# Quad_ESC_controller.net
KiCad netlist of a schematic drawn in EAGLE
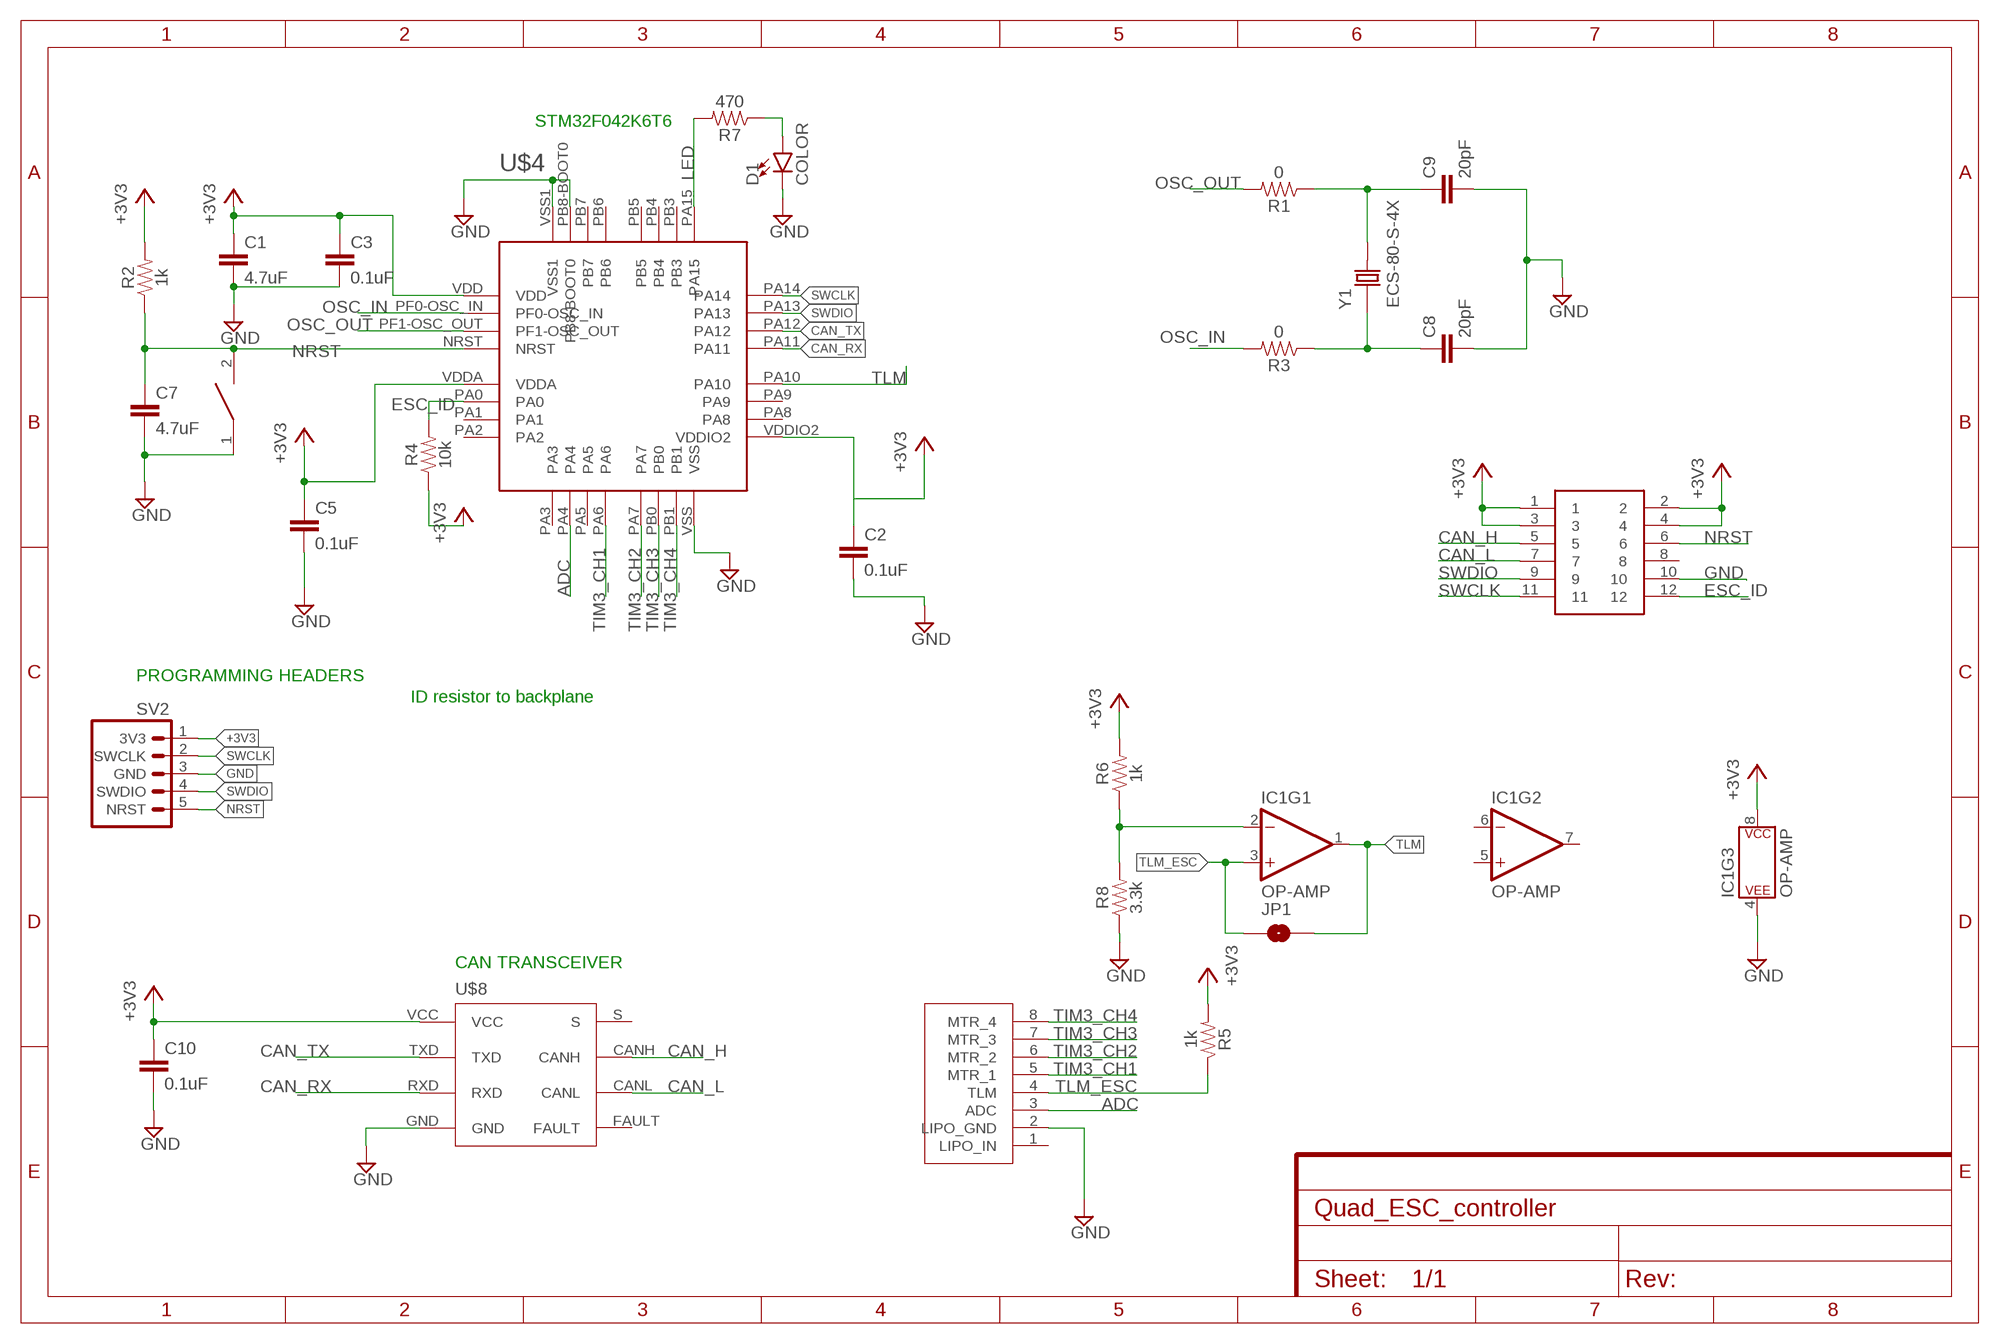
[diagram p0: schematic, sheet 1]

(export (version "E")
  (design (tool "Eeschema 10.0.6"))
  (components
    (comp (ref "C1")
      (value "4.7uF")
      (footprint "eagle-import:0603")
      (libsource (lib "eagle-import") (part "4.7UF0603"))
    )
    (comp (ref "C2")
      (value "0.1uF")
      (footprint "eagle-import:0603")
      (libsource (lib "eagle-import") (part "4.7UF0603"))
    )
    (comp (ref "C3")
      (value "0.1uF")
      (footprint "eagle-import:0603")
      (libsource (lib "eagle-import") (part "4.7UF0603"))
    )
    (comp (ref "C5")
      (value "0.1uF")
      (footprint "eagle-import:0603")
      (libsource (lib "eagle-import") (part "4.7UF0603"))
    )
    (comp (ref "C7")
      (value "4.7uF")
      (footprint "eagle-import:0603")
      (libsource (lib "eagle-import") (part "4.7UF0603"))
    )
    (comp (ref "C8")
      (value "20pF")
      (footprint "eagle-import:0603")
      (libsource (lib "eagle-import") (part "4.7UF0603"))
    )
    (comp (ref "C9")
      (value "20pF")
      (footprint "eagle-import:0603")
      (libsource (lib "eagle-import") (part "4.7UF0603"))
    )
    (comp (ref "C10")
      (value "0.1uF")
      (footprint "eagle-import:0603")
      (libsource (lib "eagle-import") (part "4.7UF0603"))
    )
    (comp (ref "D1")
      (value "COLOR")
      (footprint "eagle-import:0805")
      (libsource (lib "eagle-import") (part "LED-0805"))
    )
    (comp (ref "IC1")
      (value "OP-AMP")
      (footprint "eagle-import:SO08")
      (libsource (lib "eagle-import") (part "OPAMP-DUALU"))
    )
    (comp (ref "JP1")
      (value "JUMPER-SMT_2_NO_SILK")
      (footprint "eagle-import:SMT-JUMPER_2_NO_SILK")
      (libsource (lib "eagle-import") (part "JUMPER-SMT_2_NO_SILK"))
    )
    (comp (ref "R1")
      (value "0")
      (footprint "eagle-import:0603")
      (libsource (lib "eagle-import") (part "1KOHM-0603-1/10W-1%"))
    )
    (comp (ref "R2")
      (value "1k")
      (footprint "eagle-import:0603")
      (libsource (lib "eagle-import") (part "1KOHM-0603-1/10W-1%"))
    )
    (comp (ref "R3")
      (value "0")
      (footprint "eagle-import:0603")
      (libsource (lib "eagle-import") (part "1KOHM-0603-1/10W-1%"))
    )
    (comp (ref "R4")
      (value "10k")
      (footprint "eagle-import:0603")
      (libsource (lib "eagle-import") (part "10KOHM-0603-1/10W-1%"))
    )
    (comp (ref "R5")
      (value "1k")
      (footprint "eagle-import:0603")
      (libsource (lib "eagle-import") (part "RESISTOR0603"))
    )
    (comp (ref "R6")
      (value "1k")
      (footprint "eagle-import:0603")
      (libsource (lib "eagle-import") (part "RESISTOR0603"))
    )
    (comp (ref "R7")
      (value "470")
      (footprint "eagle-import:0603")
      (libsource (lib "eagle-import") (part "RESISTOR0603"))
    )
    (comp (ref "R8")
      (value "3.3k")
      (footprint "eagle-import:0603")
      (libsource (lib "eagle-import") (part "RESISTOR0603"))
    )
    (comp (ref "RESET")
      (value "DISCRETECOMPONENTS_SWITCH")
      (footprint "eagle-import:DISCRETECOMPONENTS_SW_2512")
      (libsource (lib "eagle-import") (part "DISCRETECOMPONENTS_SWITCH"))
    )
    (comp (ref "SV2")
      (value "3V3 -SWCLK-GND-SWDIO- NRST")
      (footprint "eagle-import:1X05")
      (libsource (lib "eagle-import") (part "SWD_CONN"))
    )
    (comp (ref "U$2")
      (value "JST-8PIN")
      (footprint "eagle-import:8PIN_CONNECTOR")
      (libsource (lib "eagle-import") (part "JST-8PIN"))
    )
    (comp (ref "U$3")
      (value "BACKPLANE_CONNECTORSESC")
      (footprint "eagle-import:BACKPLANE_CONNECTORS_ESC")
      (libsource (lib "eagle-import") (part "BACKPLANE_CONNECTORSESC"))
    )
    (comp (ref "U$4")
      (value "STM32F042K6T6")
      (footprint "eagle-import:STM32F042K6T6")
      (libsource (lib "eagle-import") (part "STM32F042K6T6"))
    )
    (comp (ref "U$8")
      (value "TCAN337D")
      (footprint "eagle-import:TCAN337D")
      (libsource (lib "eagle-import") (part "TCAN337D"))
    )
    (comp (ref "Y1")
      (value "ECS-80-S-4X")
      (footprint "eagle-import:XTAL_ECS-80-S-4X")
      (fields (field (name "DIGI-KEY_PART_NUMBER") "X1057-ND") (field (name "MF") "ECS International"))
      (libsource (lib "eagle-import") (part "ECS-80-S-4X"))
    )
  )
  (nets
    (net (code "1") (name "+3V3") (class "Default")
      (node (ref "C1") (pin "1") (pinfunction "1_1") (pintype "passive"))
      (node (ref "C10") (pin "1") (pinfunction "1_1") (pintype "passive"))
      (node (ref "C2") (pin "1") (pinfunction "1_1") (pintype "passive"))
      (node (ref "C3") (pin "1") (pinfunction "1_1") (pintype "passive"))
      (node (ref "C5") (pin "1") (pinfunction "1_1") (pintype "passive"))
      (node (ref "IC1") (pin "8") (pinfunction "P$V+_8") (pintype "bidirectional"))
      (node (ref "R2") (pin "2") (pinfunction "2_2") (pintype "passive"))
      (node (ref "R4") (pin "1") (pinfunction "1_1") (pintype "passive"))
      (node (ref "R5") (pin "2") (pinfunction "2_2") (pintype "passive"))
      (node (ref "R6") (pin "2") (pinfunction "2_2") (pintype "passive"))
      (node (ref "SV2") (pin "1") (pinfunction "3V3_1") (pintype "power_in"))
      (node (ref "U$3") (pin "1") (pinfunction "1_1") (pintype "passive"))
      (node (ref "U$3") (pin "2") (pinfunction "2_2") (pintype "passive"))
      (node (ref "U$3") (pin "3") (pinfunction "3_3") (pintype "passive"))
      (node (ref "U$3") (pin "4") (pinfunction "4_4") (pintype "passive"))
      (node (ref "U$4") (pin "VDD") (pinfunction "VDD_VDD") (pintype "bidirectional"))
      (node (ref "U$4") (pin "VDDA") (pinfunction "VDDA_VDDA") (pintype "bidirectional"))
      (node (ref "U$4") (pin "VDDIO2") (pinfunction "VDDIO2_VDDIO2") (pintype "bidirectional"))
      (node (ref "U$8") (pin "VCC") (pinfunction "VCC_VCC") (pintype "bidirectional"))
    )
    (net (code "2") (name "/ADC") (class "Default")
      (node (ref "U$2") (pin "3") (pinfunction "ADC_3") (pintype "bidirectional"))
      (node (ref "U$4") (pin "PA4") (pinfunction "PA4_PA4") (pintype "bidirectional"))
    )
    (net (code "3") (name "/CAN_H") (class "Default")
      (node (ref "U$3") (pin "5") (pinfunction "5_5") (pintype "passive"))
      (node (ref "U$8") (pin "CANH") (pinfunction "CANH_CANH") (pintype "bidirectional"))
    )
    (net (code "4") (name "/CAN_L") (class "Default")
      (node (ref "U$3") (pin "7") (pinfunction "7_7") (pintype "passive"))
      (node (ref "U$8") (pin "CANL") (pinfunction "CANL_CANL") (pintype "bidirectional"))
    )
    (net (code "5") (name "/ESC_ID") (class "Default")
      (node (ref "R4") (pin "2") (pinfunction "2_2") (pintype "passive"))
      (node (ref "U$3") (pin "12") (pinfunction "12_12") (pintype "passive"))
      (node (ref "U$4") (pin "PA0") (pinfunction "PA0_PA0") (pintype "bidirectional"))
    )
    (net (code "6") (name "/LED") (class "Default")
      (node (ref "R7") (pin "2") (pinfunction "2_2") (pintype "passive"))
      (node (ref "U$4") (pin "PA15") (pinfunction "PA15_PA15") (pintype "bidirectional"))
    )
    (net (code "7") (name "/OSC_IN") (class "Default")
      (node (ref "R3") (pin "2") (pinfunction "2_2") (pintype "passive"))
      (node (ref "U$4") (pin "PF0-OSC_IN") (pinfunction "PF0-OSC_IN_PF0-OSC_IN") (pintype "bidirectional"))
    )
    (net (code "8") (name "/OSC_OUT") (class "Default")
      (node (ref "R1") (pin "2") (pinfunction "2_2") (pintype "passive"))
      (node (ref "U$4") (pin "PF1-OSC_OUT") (pinfunction "PF1-OSC_OUT_PF1-OSC_OUT") (pintype "bidirectional"))
    )
    (net (code "9") (name "/TIM3_CH1") (class "Default")
      (node (ref "U$2") (pin "5") (pinfunction "MTR_1_5") (pintype "bidirectional"))
      (node (ref "U$4") (pin "PA6") (pinfunction "PA6_PA6") (pintype "bidirectional"))
    )
    (net (code "10") (name "/TIM3_CH2") (class "Default")
      (node (ref "U$2") (pin "6") (pinfunction "MTR_2_6") (pintype "bidirectional"))
      (node (ref "U$4") (pin "PA7") (pinfunction "PA7_PA7") (pintype "bidirectional"))
    )
    (net (code "11") (name "/TIM3_CH3") (class "Default")
      (node (ref "U$2") (pin "7") (pinfunction "MTR_3_7") (pintype "bidirectional"))
      (node (ref "U$4") (pin "PB0") (pinfunction "PB0_PB0") (pintype "bidirectional"))
    )
    (net (code "12") (name "/TIM3_CH4") (class "Default")
      (node (ref "U$2") (pin "8") (pinfunction "MTR_4_8") (pintype "bidirectional"))
      (node (ref "U$4") (pin "PB1") (pinfunction "PB1_PB1") (pintype "bidirectional"))
    )
    (net (code "13") (name "CAN_RX") (class "Default")
      (node (ref "U$4") (pin "PA11") (pinfunction "PA11_PA11") (pintype "bidirectional"))
      (node (ref "U$8") (pin "RXD") (pinfunction "RXD_RXD") (pintype "bidirectional"))
    )
    (net (code "14") (name "CAN_TX") (class "Default")
      (node (ref "U$4") (pin "PA12") (pinfunction "PA12_PA12") (pintype "bidirectional"))
      (node (ref "U$8") (pin "TXD") (pinfunction "TXD_TXD") (pintype "bidirectional"))
    )
    (net (code "15") (name "GND") (class "Default")
      (node (ref "C1") (pin "2") (pinfunction "2_2") (pintype "passive"))
      (node (ref "C10") (pin "2") (pinfunction "2_2") (pintype "passive"))
      (node (ref "C2") (pin "2") (pinfunction "2_2") (pintype "passive"))
      (node (ref "C3") (pin "2") (pinfunction "2_2") (pintype "passive"))
      (node (ref "C5") (pin "2") (pinfunction "2_2") (pintype "passive"))
      (node (ref "C7") (pin "2") (pinfunction "2_2") (pintype "passive"))
      (node (ref "C8") (pin "2") (pinfunction "2_2") (pintype "passive"))
      (node (ref "C9") (pin "2") (pinfunction "2_2") (pintype "passive"))
      (node (ref "D1") (pin "C") (pinfunction "C_C") (pintype "passive"))
      (node (ref "IC1") (pin "4") (pinfunction "P$V-_4") (pintype "bidirectional"))
      (node (ref "R8") (pin "1") (pinfunction "1_1") (pintype "passive"))
      (node (ref "RESET") (pin "1") (pinfunction "P$1_1") (pintype "bidirectional"))
      (node (ref "SV2") (pin "3") (pinfunction "GND_3") (pintype "power_in"))
      (node (ref "U$2") (pin "2") (pinfunction "LIPO_GND_2") (pintype "bidirectional"))
      (node (ref "U$3") (pin "10") (pinfunction "10_10") (pintype "passive"))
      (node (ref "U$4") (pin "PB8-BOOT0") (pinfunction "PB8-BOOT0_PB8-BOOT0") (pintype "bidirectional"))
      (node (ref "U$4") (pin "VSS") (pinfunction "VSS_VSS") (pintype "bidirectional"))
      (node (ref "U$4") (pin "VSS1") (pinfunction "VSS1_VSS1") (pintype "bidirectional"))
      (node (ref "U$8") (pin "GND") (pinfunction "GND_GND") (pintype "bidirectional"))
    )
    (net (code "16") (name "NRST") (class "Default")
      (node (ref "C7") (pin "1") (pinfunction "1_1") (pintype "passive"))
      (node (ref "R2") (pin "1") (pinfunction "1_1") (pintype "passive"))
      (node (ref "RESET") (pin "2") (pinfunction "P$2_2") (pintype "bidirectional"))
      (node (ref "SV2") (pin "5") (pinfunction "NRST_5") (pintype "open_collector"))
      (node (ref "U$3") (pin "6") (pinfunction "6_6") (pintype "passive"))
      (node (ref "U$4") (pin "NRST") (pinfunction "NRST_NRST") (pintype "bidirectional"))
    )
    (net (code "17") (name "Net-(C8-Pad1)") (class "Default")
      (node (ref "C8") (pin "1") (pinfunction "1_1") (pintype "passive"))
      (node (ref "R3") (pin "1") (pinfunction "1_1") (pintype "passive"))
      (node (ref "Y1") (pin "1") (pinfunction "1_1") (pintype "passive"))
    )
    (net (code "18") (name "Net-(C9-Pad1)") (class "Default")
      (node (ref "C9") (pin "1") (pinfunction "1_1") (pintype "passive"))
      (node (ref "R1") (pin "1") (pinfunction "1_1") (pintype "passive"))
      (node (ref "Y1") (pin "2") (pinfunction "2_2") (pintype "passive"))
    )
    (net (code "19") (name "Net-(D1-PadA)") (class "Default")
      (node (ref "D1") (pin "A") (pinfunction "A_A") (pintype "passive"))
      (node (ref "R7") (pin "1") (pinfunction "1_1") (pintype "passive"))
    )
    (net (code "20") (name "Net-(IC1A--IN)") (class "Default")
      (node (ref "IC1") (pin "2") (pinfunction "-IN_2") (pintype "input"))
      (node (ref "R6") (pin "1") (pinfunction "1_1") (pintype "passive"))
      (node (ref "R8") (pin "2") (pinfunction "2_2") (pintype "passive"))
    )
    (net (code "21") (name "SWCLK") (class "Default")
      (node (ref "SV2") (pin "2") (pinfunction "SWCLK_2") (pintype "input"))
      (node (ref "U$3") (pin "11") (pinfunction "11_11") (pintype "passive"))
      (node (ref "U$4") (pin "PA14") (pinfunction "PA14_PA14") (pintype "bidirectional"))
    )
    (net (code "22") (name "SWDIO") (class "Default")
      (node (ref "SV2") (pin "4") (pinfunction "SWDIO_4") (pintype "bidirectional"))
      (node (ref "U$3") (pin "9") (pinfunction "9_9") (pintype "passive"))
      (node (ref "U$4") (pin "PA13") (pinfunction "PA13_PA13") (pintype "bidirectional"))
    )
    (net (code "23") (name "TLM") (class "Default")
      (node (ref "IC1") (pin "1") (pinfunction "OUT_1") (pintype "output"))
      (node (ref "JP1") (pin "2") (pinfunction "2_2") (pintype "passive"))
      (node (ref "U$4") (pin "PA10") (pinfunction "PA10_PA10") (pintype "bidirectional"))
    )
    (net (code "24") (name "TLM_ESC") (class "Default")
      (node (ref "IC1") (pin "3") (pinfunction "+IN_3") (pintype "input"))
      (node (ref "JP1") (pin "1") (pinfunction "1_1") (pintype "passive"))
      (node (ref "R5") (pin "1") (pinfunction "1_1") (pintype "passive"))
      (node (ref "U$2") (pin "4") (pinfunction "TLM_4") (pintype "bidirectional"))
    )
    (net (code "25") (name "unconnected-(IC1B-+IN-Pad5)") (class "Default")
      (node (ref "IC1") (pin "5") (pinfunction "+IN_5") (pintype "input"))
    )
    (net (code "26") (name "unconnected-(IC1B--IN-Pad6)") (class "Default")
      (node (ref "IC1") (pin "6") (pinfunction "-IN_6") (pintype "input"))
    )
    (net (code "27") (name "unconnected-(IC1B-OUT-Pad7)") (class "Default")
      (node (ref "IC1") (pin "7") (pinfunction "OUT_7") (pintype "output"))
    )
    (net (code "28") (name "unconnected-(U$2-LIPO_IN-Pad1)") (class "Default")
      (node (ref "U$2") (pin "1") (pinfunction "LIPO_IN_1") (pintype "bidirectional"))
    )
    (net (code "29") (name "unconnected-(U$3-Pad8)") (class "Default")
      (node (ref "U$3") (pin "8") (pinfunction "8_8") (pintype "passive"))
    )
    (net (code "30") (name "unconnected-(U$4-PadPA1)") (class "Default")
      (node (ref "U$4") (pin "PA1") (pinfunction "PA1_PA1") (pintype "bidirectional"))
    )
    (net (code "31") (name "unconnected-(U$4-PadPA2)") (class "Default")
      (node (ref "U$4") (pin "PA2") (pinfunction "PA2_PA2") (pintype "bidirectional"))
    )
    (net (code "32") (name "unconnected-(U$4-PadPA3)") (class "Default")
      (node (ref "U$4") (pin "PA3") (pinfunction "PA3_PA3") (pintype "bidirectional"))
    )
    (net (code "33") (name "unconnected-(U$4-PadPA5)") (class "Default")
      (node (ref "U$4") (pin "PA5") (pinfunction "PA5_PA5") (pintype "bidirectional"))
    )
    (net (code "34") (name "unconnected-(U$4-PadPA8)") (class "Default")
      (node (ref "U$4") (pin "PA8") (pinfunction "PA8_PA8") (pintype "bidirectional"))
    )
    (net (code "35") (name "unconnected-(U$4-PadPA9)") (class "Default")
      (node (ref "U$4") (pin "PA9") (pinfunction "PA9_PA9") (pintype "bidirectional"))
    )
    (net (code "36") (name "unconnected-(U$4-PadPB3)") (class "Default")
      (node (ref "U$4") (pin "PB3") (pinfunction "PB3_PB3") (pintype "bidirectional"))
    )
    (net (code "37") (name "unconnected-(U$4-PadPB4)") (class "Default")
      (node (ref "U$4") (pin "PB4") (pinfunction "PB4_PB4") (pintype "bidirectional"))
    )
    (net (code "38") (name "unconnected-(U$4-PadPB5)") (class "Default")
      (node (ref "U$4") (pin "PB5") (pinfunction "PB5_PB5") (pintype "bidirectional"))
    )
    (net (code "39") (name "unconnected-(U$4-PadPB6)") (class "Default")
      (node (ref "U$4") (pin "PB6") (pinfunction "PB6_PB6") (pintype "bidirectional"))
    )
    (net (code "40") (name "unconnected-(U$4-PadPB7)") (class "Default")
      (node (ref "U$4") (pin "PB7") (pinfunction "PB7_PB7") (pintype "bidirectional"))
    )
    (net (code "41") (name "unconnected-(U$8-PadFAULT)") (class "Default")
      (node (ref "U$8") (pin "FAULT") (pinfunction "FAULT_FAULT") (pintype "bidirectional"))
    )
    (net (code "42") (name "unconnected-(U$8-PadS)") (class "Default")
      (node (ref "U$8") (pin "S") (pinfunction "S_S") (pintype "bidirectional"))
    )
  )
)
